# Adafruit_PiTFT_2_8in.net
KiCad netlist of a schematic drawn in EAGLE
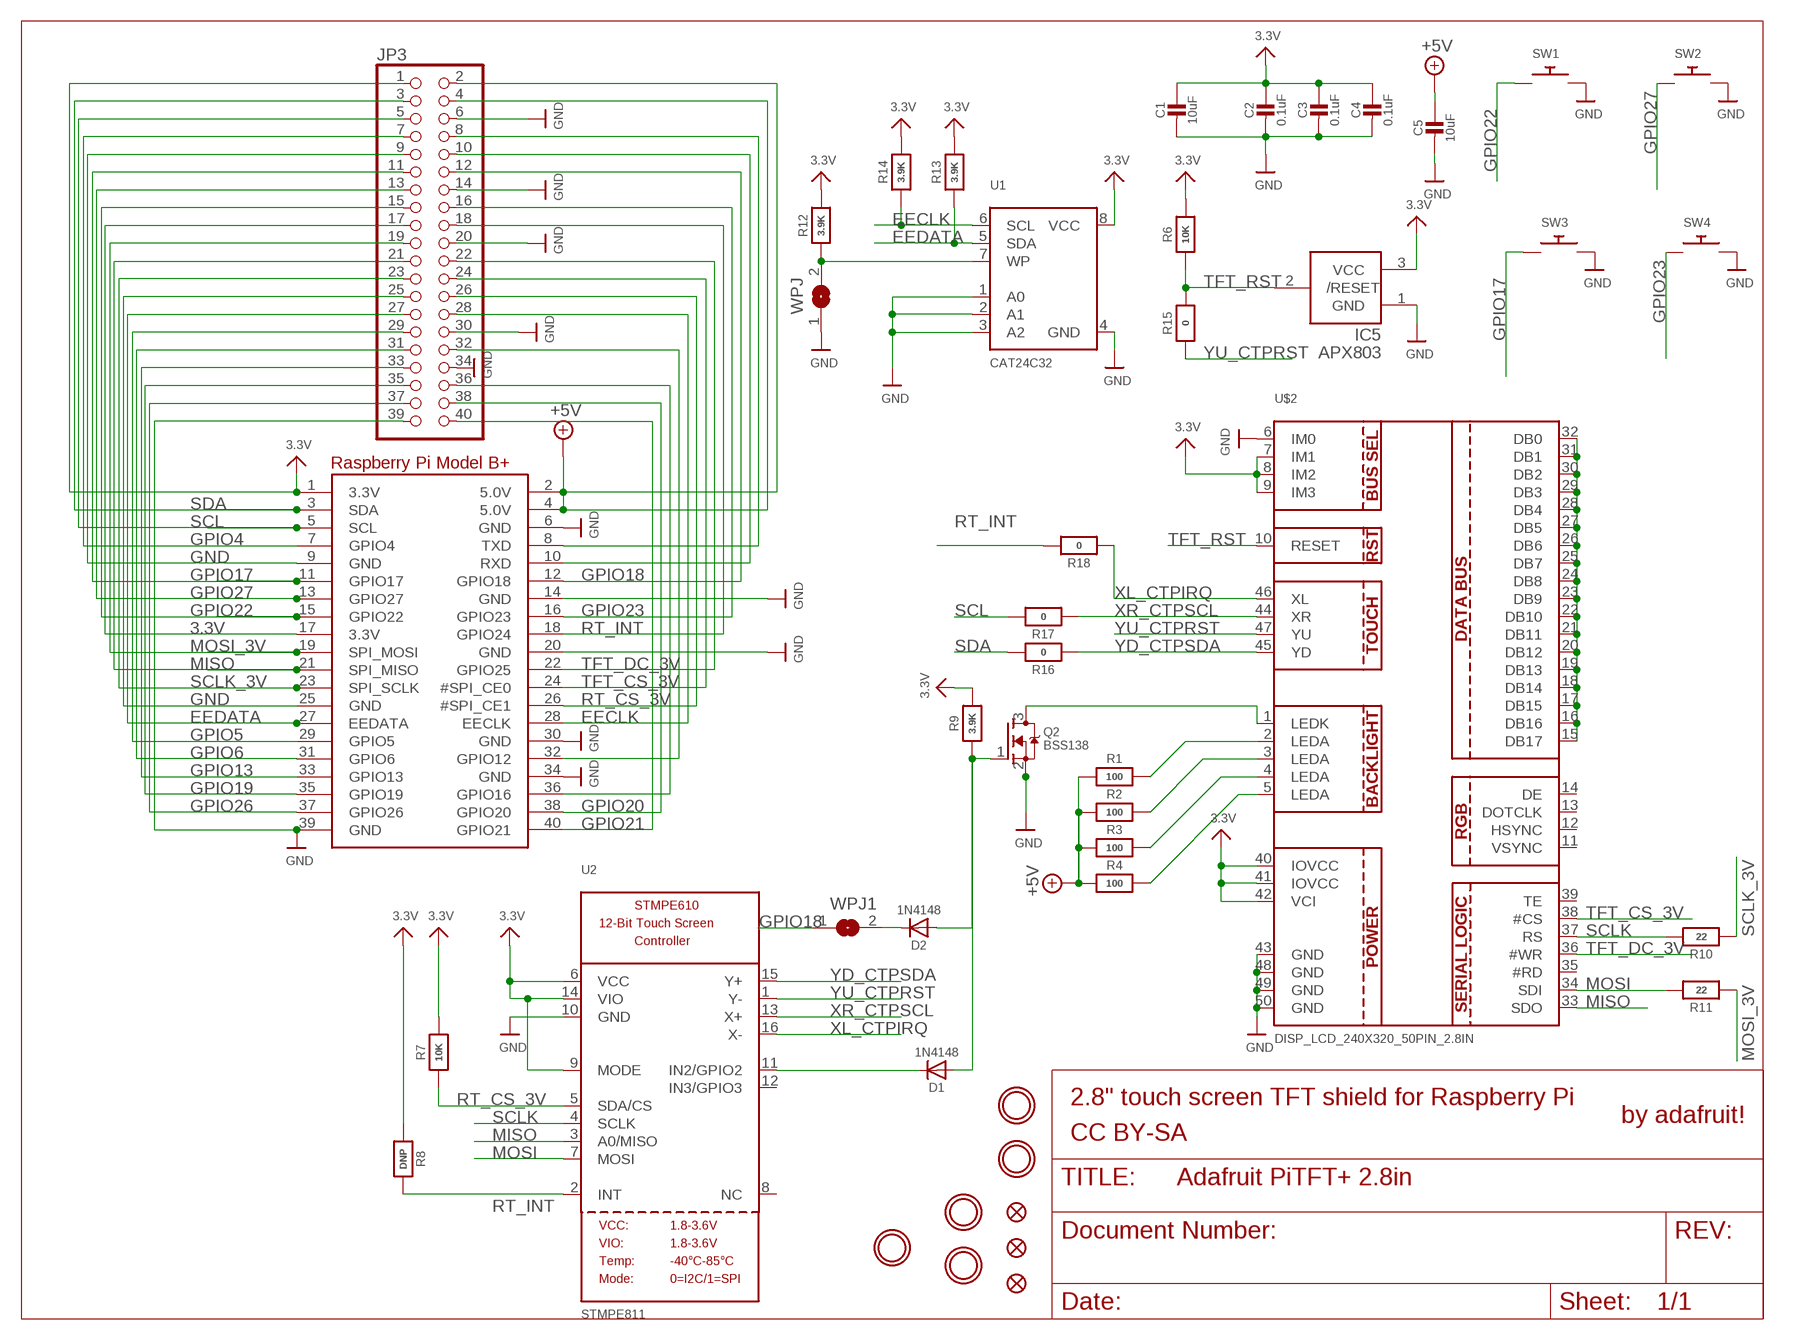
[diagram p0: schematic, sheet 1]

(export (version "E")
  (design (tool "Eeschema 10.0.6"))
  (components
    (comp (ref "C1")
      (value "10uF")
      (footprint "eagle-import:0805-NO")
      (libsource (lib "eagle-import") (part "CAP_CERAMIC0805-NOOUTLINE"))
    )
    (comp (ref "C2")
      (value "0.1uF")
      (footprint "eagle-import:0805-NO")
      (libsource (lib "eagle-import") (part "CAP_CERAMIC0805-NOOUTLINE"))
    )
    (comp (ref "C3")
      (value "0.1uF")
      (footprint "eagle-import:0805-NO")
      (libsource (lib "eagle-import") (part "CAP_CERAMIC0805-NOOUTLINE"))
    )
    (comp (ref "C4")
      (value "0.1uF")
      (footprint "eagle-import:0805-NO")
      (libsource (lib "eagle-import") (part "CAP_CERAMIC0805-NOOUTLINE"))
    )
    (comp (ref "C5")
      (value "10uF")
      (footprint "eagle-import:0805-NO")
      (libsource (lib "eagle-import") (part "CAP_CERAMIC0805-NOOUTLINE"))
    )
    (comp (ref "D1")
      (value "1N4148")
      (footprint "eagle-import:SOD-323")
      (libsource (lib "eagle-import") (part "DIODESOD-323"))
    )
    (comp (ref "D2")
      (value "1N4148")
      (footprint "eagle-import:SOD-323")
      (libsource (lib "eagle-import") (part "DIODESOD-323"))
    )
    (comp (ref "IC5")
      (value "APX803")
      (footprint "eagle-import:SOT23")
      (libsource (lib "eagle-import") (part "AXP083-SAG"))
    )
    (comp (ref "JP3")
      (value "PINHD-2X20_SMT")
      (footprint "eagle-import:2X20_SMT_MALE")
      (libsource (lib "eagle-import") (part "PINHD-2X20_SMT"))
    )
    (comp (ref "Q2")
      (value "BSS138")
      (footprint "eagle-import:SOT23-WIDE")
      (libsource (lib "eagle-import") (part "MOSFET-NWIDE"))
    )
    (comp (ref "R1")
      (value "100")
      (footprint "eagle-import:0805-NO")
      (libsource (lib "eagle-import") (part "RESISTOR0805_NOOUTLINE"))
    )
    (comp (ref "R2")
      (value "100")
      (footprint "eagle-import:0805-NO")
      (libsource (lib "eagle-import") (part "RESISTOR0805_NOOUTLINE"))
    )
    (comp (ref "R3")
      (value "100")
      (footprint "eagle-import:0805-NO")
      (libsource (lib "eagle-import") (part "RESISTOR0805_NOOUTLINE"))
    )
    (comp (ref "R4")
      (value "100")
      (footprint "eagle-import:0805-NO")
      (libsource (lib "eagle-import") (part "RESISTOR0805_NOOUTLINE"))
    )
    (comp (ref "R6")
      (value "10K")
      (footprint "eagle-import:0805-NO")
      (libsource (lib "eagle-import") (part "RESISTOR0805_NOOUTLINE"))
    )
    (comp (ref "R7")
      (value "10K")
      (footprint "eagle-import:0805-NO")
      (libsource (lib "eagle-import") (part "RESISTOR0805_NOOUTLINE"))
    )
    (comp (ref "R8")
      (value "DNP")
      (footprint "eagle-import:0805-NO")
      (libsource (lib "eagle-import") (part "RESISTOR0805_NOOUTLINE"))
    )
    (comp (ref "R9")
      (value "3.9K")
      (footprint "eagle-import:0805-NO")
      (libsource (lib "eagle-import") (part "RESISTOR0805_NOOUTLINE"))
    )
    (comp (ref "R10")
      (value "22")
      (footprint "eagle-import:0805-NO")
      (libsource (lib "eagle-import") (part "RESISTOR0805_NOOUTLINE"))
    )
    (comp (ref "R11")
      (value "22")
      (footprint "eagle-import:0805-NO")
      (libsource (lib "eagle-import") (part "RESISTOR0805_NOOUTLINE"))
    )
    (comp (ref "R12")
      (value "3.9K")
      (footprint "eagle-import:0805-NO")
      (libsource (lib "eagle-import") (part "RESISTOR0805_NOOUTLINE"))
    )
    (comp (ref "R13")
      (value "3.9K")
      (footprint "eagle-import:0805-NO")
      (libsource (lib "eagle-import") (part "RESISTOR0805_NOOUTLINE"))
    )
    (comp (ref "R14")
      (value "3.9K")
      (footprint "eagle-import:0805-NO")
      (libsource (lib "eagle-import") (part "RESISTOR0805_NOOUTLINE"))
    )
    (comp (ref "R15")
      (value "0")
      (footprint "eagle-import:0805-NO")
      (libsource (lib "eagle-import") (part "RESISTOR0805_NOOUTLINE"))
    )
    (comp (ref "R16")
      (value "0")
      (footprint "eagle-import:0805-NO")
      (libsource (lib "eagle-import") (part "RESISTOR0805_NOOUTLINE"))
    )
    (comp (ref "R17")
      (value "0")
      (footprint "eagle-import:0805-NO")
      (libsource (lib "eagle-import") (part "RESISTOR0805_NOOUTLINE"))
    )
    (comp (ref "R18")
      (value "0")
      (footprint "eagle-import:0805-NO")
      (libsource (lib "eagle-import") (part "RESISTOR0805_NOOUTLINE"))
    )
    (comp (ref "RPI1")
      (value "RASPBERRYPI_BPLUS_SHIELD_NODIM")
      (footprint "eagle-import:RASPBERRYPI_BPLUS_SHIELD_NODIM")
      (libsource (lib "eagle-import") (part "RASPBERRYPI_BPLUS_SHIELD_NODIM"))
    )
    (comp (ref "SW1")
      (value "SWITCH_PUSHBUTTONEVQ-PE")
      (footprint "eagle-import:TACT_PANA-EVQ")
      (libsource (lib "eagle-import") (part "SWITCH_PUSHBUTTONEVQ-PE"))
    )
    (comp (ref "SW2")
      (value "SWITCH_PUSHBUTTONEVQ-PE")
      (footprint "eagle-import:TACT_PANA-EVQ")
      (libsource (lib "eagle-import") (part "SWITCH_PUSHBUTTONEVQ-PE"))
    )
    (comp (ref "SW3")
      (value "SWITCH_PUSHBUTTONEVQ-PE")
      (footprint "eagle-import:TACT_PANA-EVQ")
      (libsource (lib "eagle-import") (part "SWITCH_PUSHBUTTONEVQ-PE"))
    )
    (comp (ref "SW4")
      (value "SWITCH_PUSHBUTTONEVQ-PE")
      (footprint "eagle-import:TACT_PANA-EVQ")
      (libsource (lib "eagle-import") (part "SWITCH_PUSHBUTTONEVQ-PE"))
    )
    (comp (ref "U$2")
      (value "DISP_LCD_240X320_50PIN_2.8IN")
      (footprint "eagle-import:TFT_2.83IN_240X320_50PIN")
      (libsource (lib "eagle-import") (part "DISP_LCD_240X320_50PIN_2.8IN"))
    )
    (comp (ref "U$3")
      (value "MOUNTINGHOLE3.0THIN")
      (footprint "eagle-import:MOUNTINGHOLE_3.0_PLATEDTHIN")
      (libsource (lib "eagle-import") (part "MOUNTINGHOLE3.0THIN"))
    )
    (comp (ref "U$10")
      (value "FIDUCIAL\"\"")
      (footprint "eagle-import:FIDUCIAL_1MM")
      (libsource (lib "eagle-import") (part "FIDUCIAL{dblquote}{dblquote}"))
    )
    (comp (ref "U$11")
      (value "FIDUCIAL\"\"")
      (footprint "eagle-import:FIDUCIAL_1MM")
      (libsource (lib "eagle-import") (part "FIDUCIAL{dblquote}{dblquote}"))
    )
    (comp (ref "U$15")
      (value "MOUNTINGHOLE3.0THIN")
      (footprint "eagle-import:MOUNTINGHOLE_3.0_PLATEDTHIN")
      (libsource (lib "eagle-import") (part "MOUNTINGHOLE3.0THIN"))
    )
    (comp (ref "U$16")
      (value "MOUNTINGHOLE3.0THIN")
      (footprint "eagle-import:MOUNTINGHOLE_3.0_PLATEDTHIN")
      (libsource (lib "eagle-import") (part "MOUNTINGHOLE3.0THIN"))
    )
    (comp (ref "U$17")
      (value "MOUNTINGHOLE3.0THIN")
      (footprint "eagle-import:MOUNTINGHOLE_3.0_PLATEDTHIN")
      (fields (field (name "BOM") "EXCLUDE"))
      (libsource (lib "eagle-import") (part "MOUNTINGHOLE3.0THIN"))
    )
    (comp (ref "U$18")
      (value "FIDUCIAL\"\"")
      (footprint "eagle-import:FIDUCIAL_1MM")
      (libsource (lib "eagle-import") (part "FIDUCIAL{dblquote}{dblquote}"))
    )
    (comp (ref "U$40")
      (value "MOUNTINGHOLE3.0THIN")
      (footprint "eagle-import:MOUNTINGHOLE_3.0_PLATEDTHIN")
      (libsource (lib "eagle-import") (part "MOUNTINGHOLE3.0THIN"))
    )
    (comp (ref "U1")
      (value "CAT24C32")
      (footprint "eagle-import:SOIC8_150MIL")
      (libsource (lib "eagle-import") (part "EEPROM_I2C_SOIC8_GENERIC"))
    )
    (comp (ref "U2")
      (value "STMPE811")
      (footprint "eagle-import:QFN16_3MM")
      (libsource (lib "eagle-import") (part "STMPE610"))
    )
    (comp (ref "WPJ")
      (value "SOLDERJUMPERCLOSED")
      (footprint "eagle-import:SOLDERJUMPER_CLOSEDWIRE")
      (libsource (lib "eagle-import") (part "SOLDERJUMPERCLOSED"))
    )
    (comp (ref "WPJ1")
      (value "SOLDERJUMPERCLOSED")
      (footprint "eagle-import:SOLDERJUMPER_CLOSEDWIRE")
      (libsource (lib "eagle-import") (part "SOLDERJUMPERCLOSED"))
    )
  )
  (nets
    (net (code "1") (name "+5V") (class "Default")
      (node (ref "C5") (pin "1") (pinfunction "1_1") (pintype "passive"))
      (node (ref "JP3") (pin "2") (pinfunction "2_2") (pintype "passive"))
      (node (ref "JP3") (pin "4") (pinfunction "4_4") (pintype "passive"))
      (node (ref "R1") (pin "1") (pinfunction "1_1") (pintype "passive"))
      (node (ref "R2") (pin "1") (pinfunction "1_1") (pintype "passive"))
      (node (ref "R3") (pin "1") (pinfunction "1_1") (pintype "passive"))
      (node (ref "R4") (pin "1") (pinfunction "1_1") (pintype "passive"))
      (node (ref "RPI1") (pin "2") (pinfunction "5.0V_2") (pintype "power_in"))
      (node (ref "RPI1") (pin "4") (pinfunction "5.0V_4") (pintype "power_in"))
    )
    (net (code "2") (name "/EECLK") (class "Default")
      (node (ref "JP3") (pin "28") (pinfunction "28_28") (pintype "passive"))
      (node (ref "R14") (pin "1") (pinfunction "1_1") (pintype "passive"))
      (node (ref "RPI1") (pin "28") (pinfunction "EECLK_28") (pintype "power_in"))
      (node (ref "U1") (pin "6") (pinfunction "SCL_6") (pintype "input"))
    )
    (net (code "3") (name "/EEDATA") (class "Default")
      (node (ref "JP3") (pin "27") (pinfunction "27_27") (pintype "passive"))
      (node (ref "R13") (pin "1") (pinfunction "1_1") (pintype "passive"))
      (node (ref "RPI1") (pin "27") (pinfunction "EEDATA_27") (pintype "bidirectional"))
      (node (ref "U1") (pin "5") (pinfunction "SDA_5") (pintype "bidirectional"))
    )
    (net (code "4") (name "/GPIO4") (class "Default")
      (node (ref "JP3") (pin "7") (pinfunction "7_7") (pintype "passive"))
      (node (ref "RPI1") (pin "7") (pinfunction "GPIO4_7") (pintype "bidirectional"))
    )
    (net (code "5") (name "/GPIO5") (class "Default")
      (node (ref "JP3") (pin "29") (pinfunction "29_29") (pintype "passive"))
      (node (ref "RPI1") (pin "29") (pinfunction "GPIO5_29") (pintype "bidirectional"))
    )
    (net (code "6") (name "/GPIO6") (class "Default")
      (node (ref "JP3") (pin "31") (pinfunction "31_31") (pintype "passive"))
      (node (ref "RPI1") (pin "31") (pinfunction "GPIO6_31") (pintype "power_in"))
    )
    (net (code "7") (name "/GPIO13") (class "Default")
      (node (ref "JP3") (pin "33") (pinfunction "33_33") (pintype "passive"))
      (node (ref "RPI1") (pin "33") (pinfunction "GPIO13_33") (pintype "bidirectional"))
    )
    (net (code "8") (name "/GPIO17") (class "Default")
      (node (ref "JP3") (pin "11") (pinfunction "11_11") (pintype "passive"))
      (node (ref "RPI1") (pin "11") (pinfunction "GPIO17_11") (pintype "bidirectional"))
      (node (ref "SW3") (pin "P$1") (pinfunction "P$1_P$1") (pintype "passive"))
    )
    (net (code "9") (name "/GPIO18") (class "Default")
      (node (ref "JP3") (pin "12") (pinfunction "12_12") (pintype "passive"))
      (node (ref "RPI1") (pin "12") (pinfunction "GPIO18_12") (pintype "bidirectional"))
      (node (ref "WPJ1") (pin "1") (pinfunction "1_1") (pintype "passive"))
    )
    (net (code "10") (name "/GPIO19") (class "Default")
      (node (ref "JP3") (pin "35") (pinfunction "35_35") (pintype "passive"))
      (node (ref "RPI1") (pin "35") (pinfunction "GPIO19_35") (pintype "bidirectional"))
    )
    (net (code "11") (name "/GPIO20") (class "Default")
      (node (ref "JP3") (pin "38") (pinfunction "38_38") (pintype "passive"))
      (node (ref "RPI1") (pin "38") (pinfunction "GPIO20_38") (pintype "bidirectional"))
    )
    (net (code "12") (name "/GPIO21") (class "Default")
      (node (ref "JP3") (pin "40") (pinfunction "40_40") (pintype "passive"))
      (node (ref "RPI1") (pin "40") (pinfunction "GPIO21_40") (pintype "bidirectional"))
    )
    (net (code "13") (name "/GPIO22") (class "Default")
      (node (ref "JP3") (pin "15") (pinfunction "15_15") (pintype "passive"))
      (node (ref "RPI1") (pin "15") (pinfunction "GPIO22_15") (pintype "bidirectional"))
      (node (ref "SW1") (pin "P$1") (pinfunction "P$1_P$1") (pintype "passive"))
    )
    (net (code "14") (name "/GPIO23") (class "Default")
      (node (ref "JP3") (pin "16") (pinfunction "16_16") (pintype "passive"))
      (node (ref "RPI1") (pin "16") (pinfunction "GPIO23_16") (pintype "bidirectional"))
      (node (ref "SW4") (pin "P$1") (pinfunction "P$1_P$1") (pintype "passive"))
    )
    (net (code "15") (name "/GPIO26") (class "Default")
      (node (ref "JP3") (pin "37") (pinfunction "37_37") (pintype "passive"))
      (node (ref "RPI1") (pin "37") (pinfunction "GPIO26_37") (pintype "bidirectional"))
    )
    (net (code "16") (name "/GPIO27") (class "Default")
      (node (ref "JP3") (pin "13") (pinfunction "13_13") (pintype "passive"))
      (node (ref "RPI1") (pin "13") (pinfunction "GPIO27_13") (pintype "bidirectional"))
      (node (ref "SW2") (pin "P$1") (pinfunction "P$1_P$1") (pintype "passive"))
    )
    (net (code "17") (name "/MISO") (class "Default")
      (node (ref "JP3") (pin "21") (pinfunction "21_21") (pintype "passive"))
      (node (ref "RPI1") (pin "21") (pinfunction "SPI_MISO_21") (pintype "bidirectional"))
      (node (ref "U$2") (pin "33") (pinfunction "SDO_33") (pintype "bidirectional"))
      (node (ref "U2") (pin "3") (pinfunction "A0/MISO_3") (pintype "bidirectional"))
    )
    (net (code "18") (name "/MOSI") (class "Default")
      (node (ref "R11") (pin "2") (pinfunction "2_2") (pintype "passive"))
      (node (ref "U$2") (pin "34") (pinfunction "SDI_34") (pintype "bidirectional"))
      (node (ref "U2") (pin "7") (pinfunction "MOSI_7") (pintype "input"))
    )
    (net (code "19") (name "/MOSI_3V") (class "Default")
      (node (ref "JP3") (pin "19") (pinfunction "19_19") (pintype "passive"))
      (node (ref "R11") (pin "1") (pinfunction "1_1") (pintype "passive"))
      (node (ref "RPI1") (pin "19") (pinfunction "SPI_MOSI_19") (pintype "bidirectional"))
    )
    (net (code "20") (name "/RT_CS_3V") (class "Default")
      (node (ref "JP3") (pin "26") (pinfunction "26_26") (pintype "passive"))
      (node (ref "R7") (pin "1") (pinfunction "1_1") (pintype "passive"))
      (node (ref "RPI1") (pin "26") (pinfunction "#SPI_CE1_26") (pintype "bidirectional"))
      (node (ref "U2") (pin "5") (pinfunction "SDA/CS_5") (pintype "bidirectional"))
    )
    (net (code "21") (name "/RT_INT") (class "Default")
      (node (ref "JP3") (pin "18") (pinfunction "18_18") (pintype "passive"))
      (node (ref "R18") (pin "2") (pinfunction "2_2") (pintype "passive"))
      (node (ref "R8") (pin "2") (pinfunction "2_2") (pintype "passive"))
      (node (ref "RPI1") (pin "18") (pinfunction "GPIO24_18") (pintype "bidirectional"))
      (node (ref "U2") (pin "2") (pinfunction "INT_2") (pintype "output"))
    )
    (net (code "22") (name "/SCL") (class "Default")
      (node (ref "JP3") (pin "5") (pinfunction "5_5") (pintype "passive"))
      (node (ref "R17") (pin "2") (pinfunction "2_2") (pintype "passive"))
      (node (ref "RPI1") (pin "5") (pinfunction "SCL_5") (pintype "bidirectional"))
    )
    (net (code "23") (name "/SCLK") (class "Default")
      (node (ref "R10") (pin "2") (pinfunction "2_2") (pintype "passive"))
      (node (ref "U$2") (pin "37") (pinfunction "RS_37") (pintype "bidirectional"))
      (node (ref "U2") (pin "4") (pinfunction "SCLK_4") (pintype "bidirectional"))
    )
    (net (code "24") (name "/SCLK_3V") (class "Default")
      (node (ref "JP3") (pin "23") (pinfunction "23_23") (pintype "passive"))
      (node (ref "R10") (pin "1") (pinfunction "1_1") (pintype "passive"))
      (node (ref "RPI1") (pin "23") (pinfunction "SPI_SCLK_23") (pintype "bidirectional"))
    )
    (net (code "25") (name "/SDA") (class "Default")
      (node (ref "JP3") (pin "3") (pinfunction "3_3") (pintype "passive"))
      (node (ref "R16") (pin "2") (pinfunction "2_2") (pintype "passive"))
      (node (ref "RPI1") (pin "3") (pinfunction "SDA_3") (pintype "bidirectional"))
    )
    (net (code "26") (name "/TFT_CS_3V") (class "Default")
      (node (ref "JP3") (pin "24") (pinfunction "24_24") (pintype "passive"))
      (node (ref "RPI1") (pin "24") (pinfunction "#SPI_CE0_24") (pintype "bidirectional"))
      (node (ref "U$2") (pin "38") (pinfunction "#CS_38") (pintype "bidirectional"))
    )
    (net (code "27") (name "/TFT_DC_3V") (class "Default")
      (node (ref "JP3") (pin "22") (pinfunction "22_22") (pintype "passive"))
      (node (ref "RPI1") (pin "22") (pinfunction "GPIO25_22") (pintype "bidirectional"))
      (node (ref "U$2") (pin "36") (pinfunction "#WR_36") (pintype "bidirectional"))
    )
    (net (code "28") (name "/TFT_RST") (class "Default")
      (node (ref "IC5") (pin "2") (pinfunction "/RESET_2") (pintype "output"))
      (node (ref "R15") (pin "2") (pinfunction "2_2") (pintype "passive"))
      (node (ref "R6") (pin "1") (pinfunction "1_1") (pintype "passive"))
      (node (ref "U$2") (pin "10") (pinfunction "RESET_10") (pintype "bidirectional"))
    )
    (net (code "29") (name "/XL_CTPIRQ") (class "Default")
      (node (ref "R18") (pin "1") (pinfunction "1_1") (pintype "passive"))
      (node (ref "U$2") (pin "46") (pinfunction "XL_46") (pintype "bidirectional"))
      (node (ref "U2") (pin "16") (pinfunction "X-_16") (pintype "input"))
    )
    (net (code "30") (name "/XR_CTPSCL") (class "Default")
      (node (ref "R17") (pin "1") (pinfunction "1_1") (pintype "passive"))
      (node (ref "U$2") (pin "44") (pinfunction "XR_44") (pintype "bidirectional"))
      (node (ref "U2") (pin "13") (pinfunction "X+_13") (pintype "input"))
    )
    (net (code "31") (name "/YD_CTPSDA") (class "Default")
      (node (ref "R16") (pin "1") (pinfunction "1_1") (pintype "passive"))
      (node (ref "U$2") (pin "45") (pinfunction "YD_45") (pintype "bidirectional"))
      (node (ref "U2") (pin "15") (pinfunction "Y+_15") (pintype "input"))
    )
    (net (code "32") (name "/YU_CTPRST") (class "Default")
      (node (ref "R15") (pin "1") (pinfunction "1_1") (pintype "passive"))
      (node (ref "U$2") (pin "47") (pinfunction "YU_47") (pintype "bidirectional"))
      (node (ref "U2") (pin "1") (pinfunction "Y-_1") (pintype "input"))
    )
    (net (code "33") (name "3.3V") (class "Default")
      (node (ref "C1") (pin "1") (pinfunction "1_1") (pintype "passive"))
      (node (ref "C2") (pin "1") (pinfunction "1_1") (pintype "passive"))
      (node (ref "C3") (pin "1") (pinfunction "1_1") (pintype "passive"))
      (node (ref "C4") (pin "1") (pinfunction "1_1") (pintype "passive"))
      (node (ref "IC5") (pin "3") (pinfunction "VCC_3") (pintype "power_in"))
      (node (ref "JP3") (pin "1") (pinfunction "1_1") (pintype "passive"))
      (node (ref "JP3") (pin "17") (pinfunction "17_17") (pintype "passive"))
      (node (ref "R12") (pin "2") (pinfunction "2_2") (pintype "passive"))
      (node (ref "R13") (pin "2") (pinfunction "2_2") (pintype "passive"))
      (node (ref "R14") (pin "2") (pinfunction "2_2") (pintype "passive"))
      (node (ref "R6") (pin "2") (pinfunction "2_2") (pintype "passive"))
      (node (ref "R7") (pin "2") (pinfunction "2_2") (pintype "passive"))
      (node (ref "R8") (pin "1") (pinfunction "1_1") (pintype "passive"))
      (node (ref "R9") (pin "2") (pinfunction "2_2") (pintype "passive"))
      (node (ref "RPI1") (pin "1") (pinfunction "3.3V_1") (pintype "power_in"))
      (node (ref "RPI1") (pin "17") (pinfunction "3.3V_17") (pintype "power_in"))
      (node (ref "U$2") (pin "40") (pinfunction "IOVCC_40") (pintype "bidirectional"))
      (node (ref "U$2") (pin "41") (pinfunction "IOVCC_41") (pintype "bidirectional"))
      (node (ref "U$2") (pin "42") (pinfunction "VCI_42") (pintype "bidirectional"))
      (node (ref "U$2") (pin "7") (pinfunction "IM1_7") (pintype "bidirectional"))
      (node (ref "U$2") (pin "8") (pinfunction "IM2_8") (pintype "bidirectional"))
      (node (ref "U$2") (pin "9") (pinfunction "IM3_9") (pintype "bidirectional"))
      (node (ref "U1") (pin "8") (pinfunction "VCC_8") (pintype "power_in"))
      (node (ref "U2") (pin "14") (pinfunction "VIO_14") (pintype "power_in"))
      (node (ref "U2") (pin "6") (pinfunction "VCC_6") (pintype "power_in"))
      (node (ref "U2") (pin "9") (pinfunction "MODE_9") (pintype "input"))
    )
    (net (code "34") (name "GND") (class "Default")
      (node (ref "C1") (pin "2") (pinfunction "2_2") (pintype "passive"))
      (node (ref "C2") (pin "2") (pinfunction "2_2") (pintype "passive"))
      (node (ref "C3") (pin "2") (pinfunction "2_2") (pintype "passive"))
      (node (ref "C4") (pin "2") (pinfunction "2_2") (pintype "passive"))
      (node (ref "C5") (pin "2") (pinfunction "2_2") (pintype "passive"))
      (node (ref "IC5") (pin "1") (pinfunction "GND_1") (pintype "power_in"))
      (node (ref "JP3") (pin "14") (pinfunction "14_14") (pintype "passive"))
      (node (ref "JP3") (pin "20") (pinfunction "20_20") (pintype "passive"))
      (node (ref "JP3") (pin "25") (pinfunction "25_25") (pintype "passive"))
      (node (ref "JP3") (pin "30") (pinfunction "30_30") (pintype "passive"))
      (node (ref "JP3") (pin "34") (pinfunction "34_34") (pintype "passive"))
      (node (ref "JP3") (pin "39") (pinfunction "39_39") (pintype "passive"))
      (node (ref "JP3") (pin "6") (pinfunction "6_6") (pintype "passive"))
      (node (ref "JP3") (pin "9") (pinfunction "9_9") (pintype "passive"))
      (node (ref "Q2") (pin "2") (pinfunction "S_2") (pintype "bidirectional"))
      (node (ref "RPI1") (pin "14") (pinfunction "GND_14") (pintype "power_in"))
      (node (ref "RPI1") (pin "20") (pinfunction "GND_20") (pintype "power_in"))
      (node (ref "RPI1") (pin "25") (pinfunction "GND_25") (pintype "power_in"))
      (node (ref "RPI1") (pin "30") (pinfunction "GND_30") (pintype "bidirectional"))
      (node (ref "RPI1") (pin "34") (pinfunction "GND_34") (pintype "bidirectional"))
      (node (ref "RPI1") (pin "39") (pinfunction "GND_39") (pintype "power_in"))
      (node (ref "RPI1") (pin "6") (pinfunction "GND_6") (pintype "power_in"))
      (node (ref "RPI1") (pin "9") (pinfunction "GND_9") (pintype "power_in"))
      (node (ref "SW1") (pin "P$2") (pinfunction "P$2_P$2") (pintype "passive"))
      (node (ref "SW2") (pin "P$2") (pinfunction "P$2_P$2") (pintype "passive"))
      (node (ref "SW3") (pin "P$2") (pinfunction "P$2_P$2") (pintype "passive"))
      (node (ref "SW4") (pin "P$2") (pinfunction "P$2_P$2") (pintype "passive"))
      (node (ref "U$2") (pin "43") (pinfunction "GND_43") (pintype "bidirectional"))
      (node (ref "U$2") (pin "48") (pinfunction "GND_48") (pintype "bidirectional"))
      (node (ref "U$2") (pin "49") (pinfunction "GND_49") (pintype "bidirectional"))
      (node (ref "U$2") (pin "50") (pinfunction "GND_50") (pintype "bidirectional"))
      (node (ref "U$2") (pin "6") (pinfunction "IM0_6") (pintype "bidirectional"))
      (node (ref "U1") (pin "1") (pinfunction "A0_1") (pintype "input"))
      (node (ref "U1") (pin "2") (pinfunction "A1_2") (pintype "input"))
      (node (ref "U1") (pin "3") (pinfunction "A2_3") (pintype "input"))
      (node (ref "U1") (pin "4") (pinfunction "GND_4") (pintype "power_in"))
      (node (ref "U2") (pin "10") (pinfunction "GND_10") (pintype "power_in"))
      (node (ref "WPJ") (pin "1") (pinfunction "1_1") (pintype "passive"))
    )
    (net (code "35") (name "Net-(D2-PadC)") (class "Default")
      (node (ref "D2") (pin "C") (pinfunction "C_C") (pintype "passive"))
      (node (ref "WPJ1") (pin "2") (pinfunction "2_2") (pintype "passive"))
    )
    (net (code "36") (name "Net-(Q2-D)") (class "Default")
      (node (ref "Q2") (pin "3") (pinfunction "D_3") (pintype "bidirectional"))
      (node (ref "U$2") (pin "1") (pinfunction "LEDK_1") (pintype "bidirectional"))
    )
    (net (code "37") (name "Net-(Q2-G)") (class "Default")
      (node (ref "D1") (pin "A") (pinfunction "A_A") (pintype "passive"))
      (node (ref "D2") (pin "A") (pinfunction "A_A") (pintype "passive"))
      (node (ref "Q2") (pin "1") (pinfunction "G_1") (pintype "bidirectional"))
      (node (ref "R9") (pin "1") (pinfunction "1_1") (pintype "passive"))
    )
    (net (code "38") (name "Net-(R1-Pad2)") (class "Default")
      (node (ref "R1") (pin "2") (pinfunction "2_2") (pintype "passive"))
      (node (ref "U$2") (pin "2") (pinfunction "LEDA_2") (pintype "bidirectional"))
    )
    (net (code "39") (name "Net-(R2-Pad2)") (class "Default")
      (node (ref "R2") (pin "2") (pinfunction "2_2") (pintype "passive"))
      (node (ref "U$2") (pin "3") (pinfunction "LEDA_3") (pintype "bidirectional"))
    )
    (net (code "40") (name "Net-(R3-Pad2)") (class "Default")
      (node (ref "R3") (pin "2") (pinfunction "2_2") (pintype "passive"))
      (node (ref "U$2") (pin "4") (pinfunction "LEDA_4") (pintype "bidirectional"))
    )
    (net (code "41") (name "Net-(R4-Pad2)") (class "Default")
      (node (ref "R4") (pin "2") (pinfunction "2_2") (pintype "passive"))
      (node (ref "U$2") (pin "5") (pinfunction "LEDA_5") (pintype "bidirectional"))
    )
    (net (code "42") (name "Net-(RPI1-GPIO12)") (class "Default")
      (node (ref "JP3") (pin "32") (pinfunction "32_32") (pintype "passive"))
      (node (ref "RPI1") (pin "32") (pinfunction "GPIO12_32") (pintype "bidirectional"))
    )
    (net (code "43") (name "Net-(RPI1-GPIO16)") (class "Default")
      (node (ref "JP3") (pin "36") (pinfunction "36_36") (pintype "passive"))
      (node (ref "RPI1") (pin "36") (pinfunction "GPIO16_36") (pintype "power_in"))
    )
    (net (code "44") (name "Net-(RPI1-RXD)") (class "Default")
      (node (ref "JP3") (pin "10") (pinfunction "10_10") (pintype "passive"))
      (node (ref "RPI1") (pin "10") (pinfunction "RXD_10") (pintype "bidirectional"))
    )
    (net (code "45") (name "Net-(RPI1-TXD)") (class "Default")
      (node (ref "JP3") (pin "8") (pinfunction "8_8") (pintype "passive"))
      (node (ref "RPI1") (pin "8") (pinfunction "TXD_8") (pintype "output"))
    )
    (net (code "46") (name "Net-(U$2-DB0)") (class "Default")
      (node (ref "U$2") (pin "15") (pinfunction "DB17_15") (pintype "bidirectional"))
      (node (ref "U$2") (pin "16") (pinfunction "DB16_16") (pintype "bidirectional"))
      (node (ref "U$2") (pin "17") (pinfunction "DB15_17") (pintype "bidirectional"))
      (node (ref "U$2") (pin "18") (pinfunction "DB14_18") (pintype "bidirectional"))
      (node (ref "U$2") (pin "19") (pinfunction "DB13_19") (pintype "bidirectional"))
      (node (ref "U$2") (pin "20") (pinfunction "DB12_20") (pintype "bidirectional"))
      (node (ref "U$2") (pin "21") (pinfunction "DB11_21") (pintype "bidirectional"))
      (node (ref "U$2") (pin "22") (pinfunction "DB10_22") (pintype "bidirectional"))
      (node (ref "U$2") (pin "23") (pinfunction "DB9_23") (pintype "bidirectional"))
      (node (ref "U$2") (pin "24") (pinfunction "DB8_24") (pintype "bidirectional"))
      (node (ref "U$2") (pin "25") (pinfunction "DB7_25") (pintype "bidirectional"))
      (node (ref "U$2") (pin "26") (pinfunction "DB6_26") (pintype "bidirectional"))
      (node (ref "U$2") (pin "27") (pinfunction "DB5_27") (pintype "bidirectional"))
      (node (ref "U$2") (pin "28") (pinfunction "DB4_28") (pintype "bidirectional"))
      (node (ref "U$2") (pin "29") (pinfunction "DB3_29") (pintype "bidirectional"))
      (node (ref "U$2") (pin "30") (pinfunction "DB2_30") (pintype "bidirectional"))
      (node (ref "U$2") (pin "31") (pinfunction "DB1_31") (pintype "bidirectional"))
      (node (ref "U$2") (pin "32") (pinfunction "DB0_32") (pintype "bidirectional"))
    )
    (net (code "47") (name "Net-(U1-WP)") (class "Default")
      (node (ref "R12") (pin "1") (pinfunction "1_1") (pintype "passive"))
      (node (ref "U1") (pin "7") (pinfunction "WP_7") (pintype "input"))
      (node (ref "WPJ") (pin "2") (pinfunction "2_2") (pintype "passive"))
    )
    (net (code "48") (name "Net-(U2-IN2{slash}GPIO2)") (class "Default")
      (node (ref "D1") (pin "C") (pinfunction "C_C") (pintype "passive"))
      (node (ref "U2") (pin "11") (pinfunction "IN2/GPIO2_11") (pintype "bidirectional"))
    )
    (net (code "49") (name "unconnected-(U$2-#RD-Pad35)") (class "Default")
      (node (ref "U$2") (pin "35") (pinfunction "#RD_35") (pintype "bidirectional"))
    )
    (net (code "50") (name "unconnected-(U$2-DE-Pad14)") (class "Default")
      (node (ref "U$2") (pin "14") (pinfunction "DE_14") (pintype "bidirectional"))
    )
    (net (code "51") (name "unconnected-(U$2-DOTCLK-Pad13)") (class "Default")
      (node (ref "U$2") (pin "13") (pinfunction "DOTCLK_13") (pintype "bidirectional"))
    )
    (net (code "52") (name "unconnected-(U$2-HSYNC-Pad12)") (class "Default")
      (node (ref "U$2") (pin "12") (pinfunction "HSYNC_12") (pintype "bidirectional"))
    )
    (net (code "53") (name "unconnected-(U$2-TE-Pad39)") (class "Default")
      (node (ref "U$2") (pin "39") (pinfunction "TE_39") (pintype "bidirectional"))
    )
    (net (code "54") (name "unconnected-(U$2-VSYNC-Pad11)") (class "Default")
      (node (ref "U$2") (pin "11") (pinfunction "VSYNC_11") (pintype "bidirectional"))
    )
    (net (code "55") (name "unconnected-(U2-IN3{slash}GPIO3-Pad12)") (class "Default")
      (node (ref "U2") (pin "12") (pinfunction "IN3/GPIO3_12") (pintype "bidirectional"))
    )
    (net (code "56") (name "unconnected-(U2-NC-Pad8)") (class "Default")
      (node (ref "U2") (pin "8") (pinfunction "NC_8") (pintype "no_connect"))
    )
  )
)
